# RX.net
KiCad netlist of a schematic drawn in EAGLE
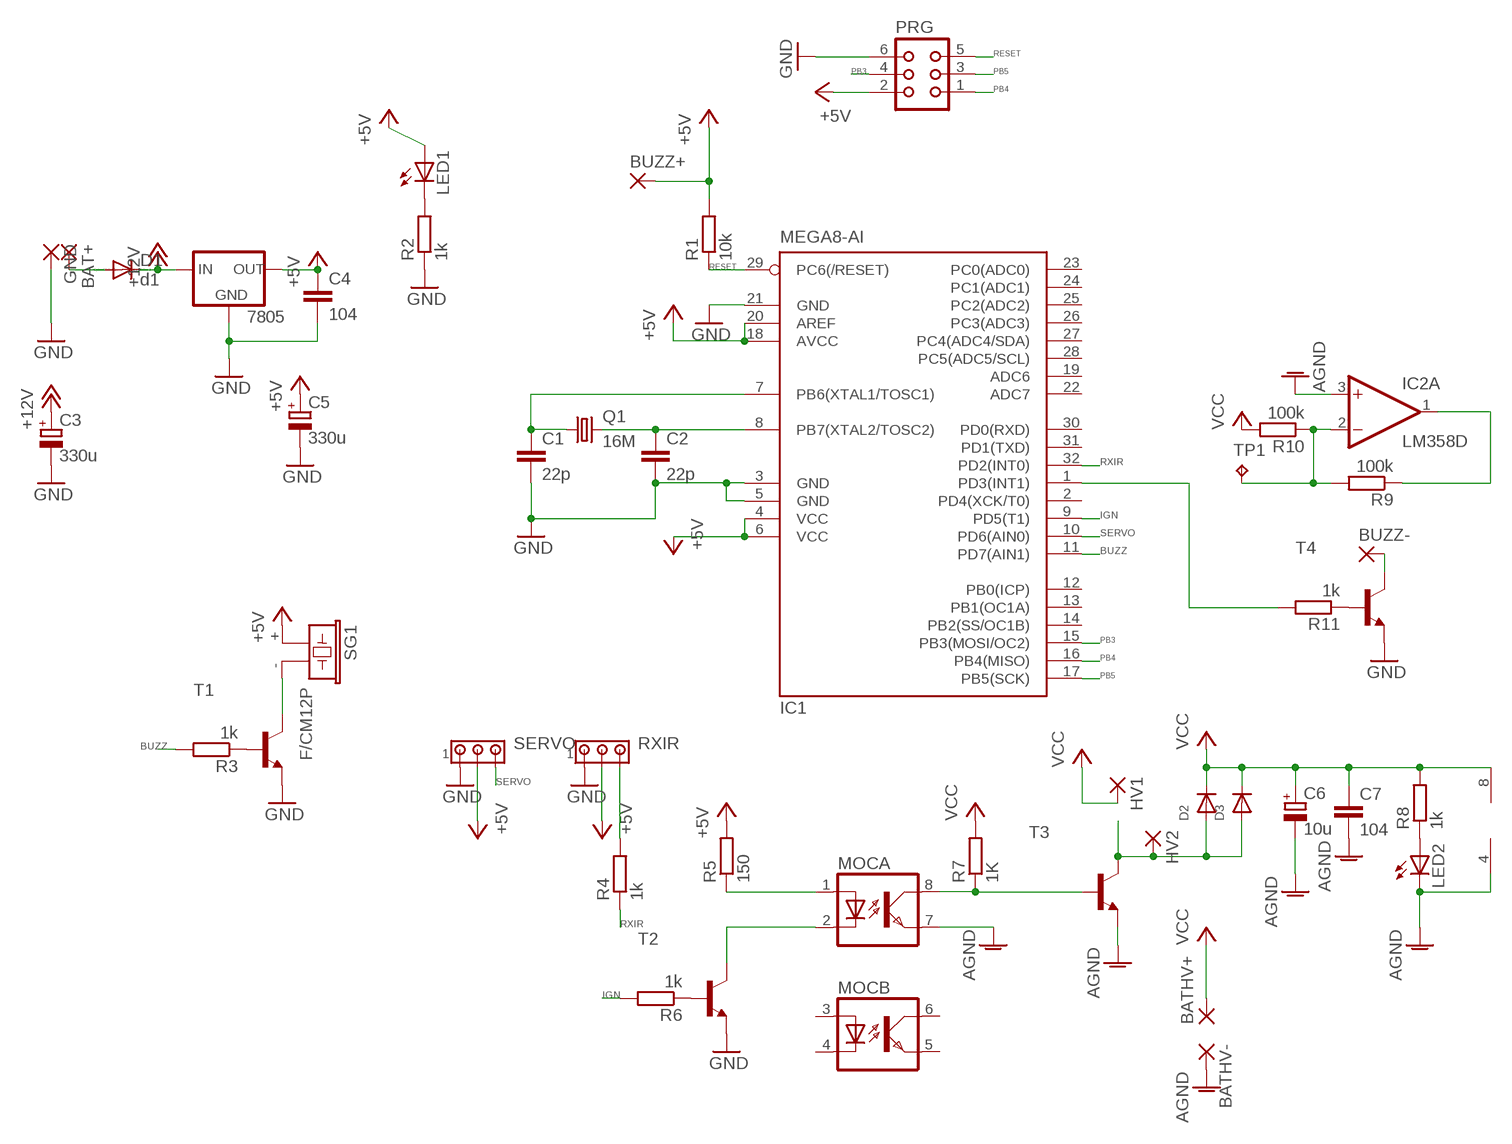
[diagram p0: schematic, sheet 1]

(export (version "E")
  (design (tool "Eeschema 10.0.6"))
  (components
    (comp (ref "7805")
      (value "78LXX")
      (footprint "eagle-import:78LXX")
      (libsource (lib "eagle-import") (part "78LXX"))
    )
    (comp (ref "BAT+")
      (value "SMD5")
      (footprint "eagle-import:SMD2,54-5,08")
      (libsource (lib "eagle-import") (part "SMD5"))
    )
    (comp (ref "BATHV+")
      (value "SMD5")
      (footprint "eagle-import:SMD2,54-5,08")
      (libsource (lib "eagle-import") (part "SMD5"))
    )
    (comp (ref "BATHV-")
      (value "SMD5")
      (footprint "eagle-import:SMD2,54-5,08")
      (libsource (lib "eagle-import") (part "SMD5"))
    )
    (comp (ref "BUZZ+")
      (value "SMD2")
      (footprint "eagle-import:SMD1,27-2,54")
      (libsource (lib "eagle-import") (part "SMD2"))
    )
    (comp (ref "BUZZ-")
      (value "SMD2")
      (footprint "eagle-import:SMD1,27-2,54")
      (libsource (lib "eagle-import") (part "SMD2"))
    )
    (comp (ref "C1")
      (value "22p")
      (footprint "eagle-import:C0805")
      (libsource (lib "eagle-import") (part "C-EUC0805"))
    )
    (comp (ref "C2")
      (value "22p")
      (footprint "eagle-import:C0805")
      (libsource (lib "eagle-import") (part "C-EUC0805"))
    )
    (comp (ref "C3")
      (value "330u")
      (footprint "eagle-import:140CLH-1010")
      (libsource (lib "eagle-import") (part "CPOL-EU140CLH-1010"))
    )
    (comp (ref "C4")
      (value "104")
      (footprint "eagle-import:C0805")
      (libsource (lib "eagle-import") (part "C-EUC0805"))
    )
    (comp (ref "C5")
      (value "330u")
      (footprint "eagle-import:140CLH-1010")
      (libsource (lib "eagle-import") (part "CPOL-EU140CLH-1010"))
    )
    (comp (ref "C6")
      (value "10u")
      (footprint "eagle-import:140CLH-0810")
      (libsource (lib "eagle-import") (part "CPOL-EU140CLH-0810"))
    )
    (comp (ref "C7")
      (value "104")
      (footprint "eagle-import:C0805")
      (libsource (lib "eagle-import") (part "C-EUC0805"))
    )
    (comp (ref "D1")
      (value "d1")
      (footprint "eagle-import:SOD-123_MINI-SMA")
      (libsource (lib "eagle-import") (part "CGRM400-G7"))
    )
    (comp (ref "D2")
      (value "DIODE_SOD-123FL")
      (footprint "eagle-import:SOD-123FL")
      (libsource (lib "eagle-import") (part "DIODE_SOD-123FL"))
    )
    (comp (ref "D3")
      (value "DIODE_SOD-123FL")
      (footprint "eagle-import:SOD-123FL")
      (libsource (lib "eagle-import") (part "DIODE_SOD-123FL"))
    )
    (comp (ref "GND")
      (value "SMD5")
      (footprint "eagle-import:SMD2,54-5,08")
      (libsource (lib "eagle-import") (part "SMD5"))
    )
    (comp (ref "HV1")
      (value "SMD5")
      (footprint "eagle-import:SMD2,54-5,08")
      (libsource (lib "eagle-import") (part "SMD5"))
    )
    (comp (ref "HV2")
      (value "SMD5")
      (footprint "eagle-import:SMD2,54-5,08")
      (libsource (lib "eagle-import") (part "SMD5"))
    )
    (comp (ref "IC1")
      (value "MEGA8-AI")
      (footprint "eagle-import:TQFP32-08")
      (fields (field (name "MPN") "ATMEGA8-16AU"))
      (libsource (lib "eagle-import") (part "MEGA8-AI"))
    )
    (comp (ref "IC2")
      (value "LM358D")
      (footprint "eagle-import:SO08")
      (libsource (lib "eagle-import") (part "LM358D"))
    )
    (comp (ref "LED1")
      (value "LED3MM")
      (footprint "eagle-import:LED3MM")
      (libsource (lib "eagle-import") (part "LED3MM"))
    )
    (comp (ref "LED2")
      (value "LEDCHIPLED_0805")
      (footprint "eagle-import:CHIPLED_0805")
      (libsource (lib "eagle-import") (part "LEDCHIPLED_0805"))
    )
    (comp (ref "MOC")
      (value "MOCD207M")
      (footprint "eagle-import:SOIC08-FAIRCHILD")
      (fields (field (name "MF") "FAIRCHILD SEMICONDUCTOR") (field (name "MPN") "MOCD207-M"))
      (libsource (lib "eagle-import") (part "MOCD20M7"))
    )
    (comp (ref "PRG")
      (value "CON06")
      (footprint "eagle-import:CON06")
      (libsource (lib "eagle-import") (part "CON06"))
    )
    (comp (ref "Q1")
      (value "16M")
      (footprint "eagle-import:HC49UP")
      (libsource (lib "eagle-import") (part "CRYSTALHC49UP"))
    )
    (comp (ref "R1")
      (value "10k")
      (footprint "eagle-import:M1206")
      (libsource (lib "eagle-import") (part "R-EU_M1206"))
    )
    (comp (ref "R2")
      (value "1k")
      (footprint "eagle-import:M1206")
      (libsource (lib "eagle-import") (part "R-EU_M1206"))
    )
    (comp (ref "R3")
      (value "1k")
      (footprint "eagle-import:M1206")
      (libsource (lib "eagle-import") (part "R-EU_M1206"))
    )
    (comp (ref "R4")
      (value "1k")
      (footprint "eagle-import:M1206")
      (libsource (lib "eagle-import") (part "R-EU_M1206"))
    )
    (comp (ref "R5")
      (value "150")
      (footprint "eagle-import:M1206")
      (libsource (lib "eagle-import") (part "R-EU_M1206"))
    )
    (comp (ref "R6")
      (value "1k")
      (footprint "eagle-import:M1206")
      (libsource (lib "eagle-import") (part "R-EU_M1206"))
    )
    (comp (ref "R7")
      (value "1K")
      (footprint "eagle-import:M1206")
      (libsource (lib "eagle-import") (part "R-EU_M1206"))
    )
    (comp (ref "R8")
      (value "1k")
      (footprint "eagle-import:M1206")
      (libsource (lib "eagle-import") (part "R-EU_M1206"))
    )
    (comp (ref "R9")
      (value "100k")
      (footprint "eagle-import:M1206")
      (libsource (lib "eagle-import") (part "R-EU_M1206"))
    )
    (comp (ref "R10")
      (value "100k")
      (footprint "eagle-import:M1206")
      (libsource (lib "eagle-import") (part "R-EU_M1206"))
    )
    (comp (ref "R11")
      (value "1k")
      (footprint "eagle-import:M1206")
      (libsource (lib "eagle-import") (part "R-EU_M1206"))
    )
    (comp (ref "RXIR")
      (value "MTA03-100")
      (footprint "eagle-import:10X03MTA")
      (libsource (lib "eagle-import") (part "MTA03-100"))
    )
    (comp (ref "SERVO")
      (value "MTA03-100")
      (footprint "eagle-import:10X03MTA")
      (libsource (lib "eagle-import") (part "MTA03-100"))
    )
    (comp (ref "SG1")
      (value "F/CM12P")
      (footprint "eagle-import:F_CM12P")
      (libsource (lib "eagle-import") (part "F/CM12P"))
    )
    (comp (ref "T1")
      (value "MMBT2222ALT1-NPN-SOT23-BEC")
      (footprint "eagle-import:SOT23-BEC")
      (libsource (lib "eagle-import") (part "-NPN-SOT23-BECMMBT2222ALT1"))
    )
    (comp (ref "T2")
      (value "MMBT2222ALT1-NPN-SOT23-BEC")
      (footprint "eagle-import:SOT23-BEC")
      (libsource (lib "eagle-import") (part "-NPN-SOT23-BECMMBT2222ALT1"))
    )
    (comp (ref "T3")
      (value "MMBT2222ALT1-NPN-SOT23-BEC")
      (footprint "eagle-import:SOT23-BEC")
      (libsource (lib "eagle-import") (part "-NPN-SOT23-BECMMBT2222ALT1"))
    )
    (comp (ref "T4")
      (value "MMBT2222ALT1-NPN-SOT23-BEC")
      (footprint "eagle-import:SOT23-BEC")
      (libsource (lib "eagle-import") (part "-NPN-SOT23-BECMMBT2222ALT1"))
    )
    (comp (ref "TP1")
      (value "TPTP10R")
      (footprint "eagle-import:TP10R")
      (libsource (lib "eagle-import") (part "TPTP10R"))
    )
  )
  (nets
    (net (code "1") (name "+5V") (class "Default")
      (node (ref "7805") (pin "OUT") (pinfunction "OUT_OUT") (pintype "passive"))
      (node (ref "BUZZ+") (pin "1") (pinfunction "P_1") (pintype "passive"))
      (node (ref "C4") (pin "1") (pinfunction "1_1") (pintype "passive"))
      (node (ref "C5") (pin "+") (pinfunction "+_+") (pintype "passive"))
      (node (ref "IC1") (pin "18") (pinfunction "AVCC_18") (pintype "power_in"))
      (node (ref "IC1") (pin "20") (pinfunction "AREF_20") (pintype "passive"))
      (node (ref "IC1") (pin "4") (pinfunction "VCC_4") (pintype "power_in"))
      (node (ref "IC1") (pin "6") (pinfunction "VCC_6") (pintype "power_in"))
      (node (ref "LED1") (pin "A") (pinfunction "A_A") (pintype "passive"))
      (node (ref "PRG") (pin "2") (pinfunction "2_2") (pintype "passive"))
      (node (ref "R1") (pin "2") (pinfunction "2_2") (pintype "passive"))
      (node (ref "R5") (pin "2") (pinfunction "2_2") (pintype "passive"))
      (node (ref "RXIR") (pin "2") (pinfunction "2_2") (pintype "passive"))
      (node (ref "SERVO") (pin "2") (pinfunction "2_2") (pintype "passive"))
      (node (ref "SG1") (pin "+") (pinfunction "1_+") (pintype "passive"))
    )
    (net (code "2") (name "+12V") (class "Default")
      (node (ref "7805") (pin "IN") (pinfunction "IN_IN") (pintype "input"))
      (node (ref "C3") (pin "+") (pinfunction "+_+") (pintype "passive"))
      (node (ref "D1") (pin "C") (pinfunction "C_C") (pintype "passive"))
    )
    (net (code "3") (name "/BUZZ") (class "Default")
      (node (ref "IC1") (pin "11") (pinfunction "PD7(AIN1)_11") (pintype "bidirectional"))
      (node (ref "R3") (pin "2") (pinfunction "2_2") (pintype "passive"))
    )
    (net (code "4") (name "/IGN") (class "Default")
      (node (ref "IC1") (pin "9") (pinfunction "PD5(T1)_9") (pintype "bidirectional"))
      (node (ref "R6") (pin "2") (pinfunction "2_2") (pintype "passive"))
    )
    (net (code "5") (name "/PB3") (class "Default")
      (node (ref "IC1") (pin "15") (pinfunction "PB3(MOSI/OC2)_15") (pintype "bidirectional"))
      (node (ref "PRG") (pin "4") (pinfunction "4_4") (pintype "passive"))
    )
    (net (code "6") (name "/PB4") (class "Default")
      (node (ref "IC1") (pin "16") (pinfunction "PB4(MISO)_16") (pintype "bidirectional"))
      (node (ref "PRG") (pin "1") (pinfunction "1_1") (pintype "passive"))
    )
    (net (code "7") (name "/PB5") (class "Default")
      (node (ref "IC1") (pin "17") (pinfunction "PB5(SCK)_17") (pintype "bidirectional"))
      (node (ref "PRG") (pin "3") (pinfunction "3_3") (pintype "passive"))
    )
    (net (code "8") (name "/RESET") (class "Default")
      (node (ref "IC1") (pin "29") (pinfunction "PC6(/RESET)_29") (pintype "bidirectional"))
      (node (ref "PRG") (pin "5") (pinfunction "5_5") (pintype "passive"))
      (node (ref "R1") (pin "1") (pinfunction "1_1") (pintype "passive"))
    )
    (net (code "9") (name "/RXIR") (class "Default")
      (node (ref "IC1") (pin "32") (pinfunction "PD2(INT0)_32") (pintype "bidirectional"))
      (node (ref "R4") (pin "1") (pinfunction "1_1") (pintype "passive"))
    )
    (net (code "10") (name "/SERVO") (class "Default")
      (node (ref "IC1") (pin "10") (pinfunction "PD6(AIN0)_10") (pintype "bidirectional"))
      (node (ref "SERVO") (pin "3") (pinfunction "3_3") (pintype "passive"))
    )
    (net (code "11") (name "AGND") (class "Default")
      (node (ref "BATHV-") (pin "1") (pinfunction "P_1") (pintype "passive"))
      (node (ref "C6") (pin "-") (pinfunction "-_-") (pintype "passive"))
      (node (ref "C7") (pin "2") (pinfunction "2_2") (pintype "passive"))
      (node (ref "IC2") (pin "3") (pinfunction "+IN_3") (pintype "input"))
      (node (ref "IC2") (pin "4") (pinfunction "V-_4") (pintype "power_in"))
      (node (ref "LED2") (pin "C") (pinfunction "C_C") (pintype "passive"))
      (node (ref "MOC") (pin "7") (pinfunction "EMIT_7") (pintype "passive"))
      (node (ref "T3") (pin "E") (pinfunction "E_E") (pintype "passive"))
    )
    (net (code "12") (name "GND") (class "Default")
      (node (ref "7805") (pin "GND") (pinfunction "GND_GND") (pintype "input"))
      (node (ref "C1") (pin "2") (pinfunction "2_2") (pintype "passive"))
      (node (ref "C2") (pin "2") (pinfunction "2_2") (pintype "passive"))
      (node (ref "C3") (pin "-") (pinfunction "-_-") (pintype "passive"))
      (node (ref "C4") (pin "2") (pinfunction "2_2") (pintype "passive"))
      (node (ref "C5") (pin "-") (pinfunction "-_-") (pintype "passive"))
      (node (ref "GND") (pin "1") (pinfunction "P_1") (pintype "passive"))
      (node (ref "IC1") (pin "21") (pinfunction "GND_21") (pintype "power_in"))
      (node (ref "IC1") (pin "3") (pinfunction "GND_3") (pintype "power_in"))
      (node (ref "IC1") (pin "5") (pinfunction "GND_5") (pintype "power_in"))
      (node (ref "PRG") (pin "6") (pinfunction "6_6") (pintype "passive"))
      (node (ref "R2") (pin "1") (pinfunction "1_1") (pintype "passive"))
      (node (ref "RXIR") (pin "1") (pinfunction "1_1") (pintype "passive"))
      (node (ref "SERVO") (pin "1") (pinfunction "1_1") (pintype "passive"))
      (node (ref "T1") (pin "E") (pinfunction "E_E") (pintype "passive"))
      (node (ref "T2") (pin "E") (pinfunction "E_E") (pintype "passive"))
      (node (ref "T4") (pin "E") (pinfunction "E_E") (pintype "passive"))
    )
    (net (code "13") (name "Net-(BAT+-P)") (class "Default")
      (node (ref "BAT+") (pin "1") (pinfunction "P_1") (pintype "passive"))
      (node (ref "D1") (pin "A") (pinfunction "A_A") (pintype "passive"))
    )
    (net (code "14") (name "Net-(BUZZ--P)") (class "Default")
      (node (ref "BUZZ-") (pin "1") (pinfunction "P_1") (pintype "passive"))
      (node (ref "T4") (pin "C") (pinfunction "C_C") (pintype "passive"))
    )
    (net (code "15") (name "Net-(HV2-P)") (class "Default")
      (node (ref "D2") (pin "A") (pinfunction "A_A") (pintype "passive"))
      (node (ref "D3") (pin "A") (pinfunction "A_A") (pintype "passive"))
      (node (ref "HV2") (pin "1") (pinfunction "P_1") (pintype "passive"))
      (node (ref "T3") (pin "C") (pinfunction "C_C") (pintype "passive"))
    )
    (net (code "16") (name "Net-(IC1-PB6(XTAL1{slash}TOSC1))") (class "Default")
      (node (ref "C1") (pin "1") (pinfunction "1_1") (pintype "passive"))
      (node (ref "IC1") (pin "7") (pinfunction "PB6(XTAL1/TOSC1)_7") (pintype "bidirectional"))
      (node (ref "Q1") (pin "1") (pinfunction "1_1") (pintype "passive"))
    )
    (net (code "17") (name "Net-(IC1-PB7(XTAL2{slash}TOSC2))") (class "Default")
      (node (ref "C2") (pin "1") (pinfunction "1_1") (pintype "passive"))
      (node (ref "IC1") (pin "8") (pinfunction "PB7(XTAL2/TOSC2)_8") (pintype "bidirectional"))
      (node (ref "Q1") (pin "2") (pinfunction "2_2") (pintype "passive"))
    )
    (net (code "18") (name "Net-(IC1-PD3(INT1))") (class "Default")
      (node (ref "IC1") (pin "1") (pinfunction "PD3(INT1)_1") (pintype "bidirectional"))
      (node (ref "R11") (pin "2") (pinfunction "2_2") (pintype "passive"))
    )
    (net (code "19") (name "Net-(IC2A--IN)") (class "Default")
      (node (ref "IC2") (pin "2") (pinfunction "-IN_2") (pintype "input"))
      (node (ref "R10") (pin "1") (pinfunction "1_1") (pintype "passive"))
      (node (ref "R9") (pin "2") (pinfunction "2_2") (pintype "passive"))
      (node (ref "TP1") (pin "TP") (pinfunction "TP_TP") (pintype "input"))
    )
    (net (code "20") (name "Net-(IC2A-OUT)") (class "Default")
      (node (ref "IC2") (pin "1") (pinfunction "OUT_1") (pintype "output"))
      (node (ref "R9") (pin "1") (pinfunction "1_1") (pintype "passive"))
    )
    (net (code "21") (name "Net-(LED1-C)") (class "Default")
      (node (ref "LED1") (pin "K") (pinfunction "C_K") (pintype "passive"))
      (node (ref "R2") (pin "2") (pinfunction "2_2") (pintype "passive"))
    )
    (net (code "22") (name "Net-(LED2-PadA)") (class "Default")
      (node (ref "LED2") (pin "A") (pinfunction "A_A") (pintype "passive"))
      (node (ref "R8") (pin "1") (pinfunction "1_1") (pintype "passive"))
    )
    (net (code "23") (name "Net-(MOCA-A)") (class "Default")
      (node (ref "MOC") (pin "1") (pinfunction "A_1") (pintype "passive"))
      (node (ref "R5") (pin "1") (pinfunction "1_1") (pintype "passive"))
    )
    (net (code "24") (name "Net-(MOCA-C)") (class "Default")
      (node (ref "MOC") (pin "2") (pinfunction "C_2") (pintype "passive"))
      (node (ref "T2") (pin "C") (pinfunction "C_C") (pintype "passive"))
    )
    (net (code "25") (name "Net-(MOCA-COL)") (class "Default")
      (node (ref "MOC") (pin "8") (pinfunction "COL_8") (pintype "passive"))
      (node (ref "R7") (pin "1") (pinfunction "1_1") (pintype "passive"))
      (node (ref "T3") (pin "B") (pinfunction "B_B") (pintype "passive"))
    )
    (net (code "26") (name "Net-(R3-Pad1)") (class "Default")
      (node (ref "R3") (pin "1") (pinfunction "1_1") (pintype "passive"))
      (node (ref "T1") (pin "B") (pinfunction "B_B") (pintype "passive"))
    )
    (net (code "27") (name "Net-(R4-Pad2)") (class "Default")
      (node (ref "R4") (pin "2") (pinfunction "2_2") (pintype "passive"))
      (node (ref "RXIR") (pin "3") (pinfunction "3_3") (pintype "passive"))
    )
    (net (code "28") (name "Net-(R6-Pad1)") (class "Default")
      (node (ref "R6") (pin "1") (pinfunction "1_1") (pintype "passive"))
      (node (ref "T2") (pin "B") (pinfunction "B_B") (pintype "passive"))
    )
    (net (code "29") (name "Net-(R11-Pad1)") (class "Default")
      (node (ref "R11") (pin "1") (pinfunction "1_1") (pintype "passive"))
      (node (ref "T4") (pin "B") (pinfunction "B_B") (pintype "passive"))
    )
    (net (code "30") (name "Net-(SG1-2)") (class "Default")
      (node (ref "SG1") (pin "-") (pinfunction "2_-") (pintype "passive"))
      (node (ref "T1") (pin "C") (pinfunction "C_C") (pintype "passive"))
    )
    (net (code "31") (name "VCC") (class "Default")
      (node (ref "BATHV+") (pin "1") (pinfunction "P_1") (pintype "passive"))
      (node (ref "C6") (pin "+") (pinfunction "+_+") (pintype "passive"))
      (node (ref "C7") (pin "1") (pinfunction "1_1") (pintype "passive"))
      (node (ref "D2") (pin "C") (pinfunction "C_C") (pintype "passive"))
      (node (ref "D3") (pin "C") (pinfunction "C_C") (pintype "passive"))
      (node (ref "HV1") (pin "1") (pinfunction "P_1") (pintype "passive"))
      (node (ref "IC2") (pin "8") (pinfunction "V+_8") (pintype "power_in"))
      (node (ref "R10") (pin "2") (pinfunction "2_2") (pintype "passive"))
      (node (ref "R7") (pin "2") (pinfunction "2_2") (pintype "passive"))
      (node (ref "R8") (pin "2") (pinfunction "2_2") (pintype "passive"))
    )
    (net (code "32") (name "unconnected-(IC1-ADC6-Pad19)") (class "Default")
      (node (ref "IC1") (pin "19") (pinfunction "ADC6_19") (pintype "bidirectional"))
    )
    (net (code "33") (name "unconnected-(IC1-ADC7-Pad22)") (class "Default")
      (node (ref "IC1") (pin "22") (pinfunction "ADC7_22") (pintype "bidirectional"))
    )
    (net (code "34") (name "unconnected-(IC1-PB0(ICP)-Pad12)") (class "Default")
      (node (ref "IC1") (pin "12") (pinfunction "PB0(ICP)_12") (pintype "bidirectional"))
    )
    (net (code "35") (name "unconnected-(IC1-PB1(OC1A)-Pad13)") (class "Default")
      (node (ref "IC1") (pin "13") (pinfunction "PB1(OC1A)_13") (pintype "bidirectional"))
    )
    (net (code "36") (name "unconnected-(IC1-PB2(SS{slash}OC1B)-Pad14)") (class "Default")
      (node (ref "IC1") (pin "14") (pinfunction "PB2(SS/OC1B)_14") (pintype "bidirectional"))
    )
    (net (code "37") (name "unconnected-(IC1-PC0(ADC0)-Pad23)") (class "Default")
      (node (ref "IC1") (pin "23") (pinfunction "PC0(ADC0)_23") (pintype "bidirectional"))
    )
    (net (code "38") (name "unconnected-(IC1-PC1(ADC1)-Pad24)") (class "Default")
      (node (ref "IC1") (pin "24") (pinfunction "PC1(ADC1)_24") (pintype "bidirectional"))
    )
    (net (code "39") (name "unconnected-(IC1-PC2(ADC2)-Pad25)") (class "Default")
      (node (ref "IC1") (pin "25") (pinfunction "PC2(ADC2)_25") (pintype "bidirectional"))
    )
    (net (code "40") (name "unconnected-(IC1-PC3(ADC3)-Pad26)") (class "Default")
      (node (ref "IC1") (pin "26") (pinfunction "PC3(ADC3)_26") (pintype "bidirectional"))
    )
    (net (code "41") (name "unconnected-(IC1-PC4(ADC4{slash}SDA)-Pad27)") (class "Default")
      (node (ref "IC1") (pin "27") (pinfunction "PC4(ADC4/SDA)_27") (pintype "bidirectional"))
    )
    (net (code "42") (name "unconnected-(IC1-PC5(ADC5{slash}SCL)-Pad28)") (class "Default")
      (node (ref "IC1") (pin "28") (pinfunction "PC5(ADC5/SCL)_28") (pintype "bidirectional"))
    )
    (net (code "43") (name "unconnected-(IC1-PD0(RXD)-Pad30)") (class "Default")
      (node (ref "IC1") (pin "30") (pinfunction "PD0(RXD)_30") (pintype "bidirectional"))
    )
    (net (code "44") (name "unconnected-(IC1-PD1(TXD)-Pad31)") (class "Default")
      (node (ref "IC1") (pin "31") (pinfunction "PD1(TXD)_31") (pintype "bidirectional"))
    )
    (net (code "45") (name "unconnected-(IC1-PD4(XCK{slash}T0)-Pad2)") (class "Default")
      (node (ref "IC1") (pin "2") (pinfunction "PD4(XCK/T0)_2") (pintype "bidirectional"))
    )
    (net (code "46") (name "unconnected-(MOCB-A-Pad3)") (class "Default")
      (node (ref "MOC") (pin "3") (pinfunction "A_3") (pintype "passive"))
    )
    (net (code "47") (name "unconnected-(MOCB-C-Pad4)") (class "Default")
      (node (ref "MOC") (pin "4") (pinfunction "C_4") (pintype "passive"))
    )
    (net (code "48") (name "unconnected-(MOCB-COL-Pad6)") (class "Default")
      (node (ref "MOC") (pin "6") (pinfunction "COL_6") (pintype "passive"))
    )
    (net (code "49") (name "unconnected-(MOCB-EMIT-Pad5)") (class "Default")
      (node (ref "MOC") (pin "5") (pinfunction "EMIT_5") (pintype "passive"))
    )
  )
)
